# BoostConverter_using_ATmega328P.net
KiCad netlist of a schematic drawn in EAGLE
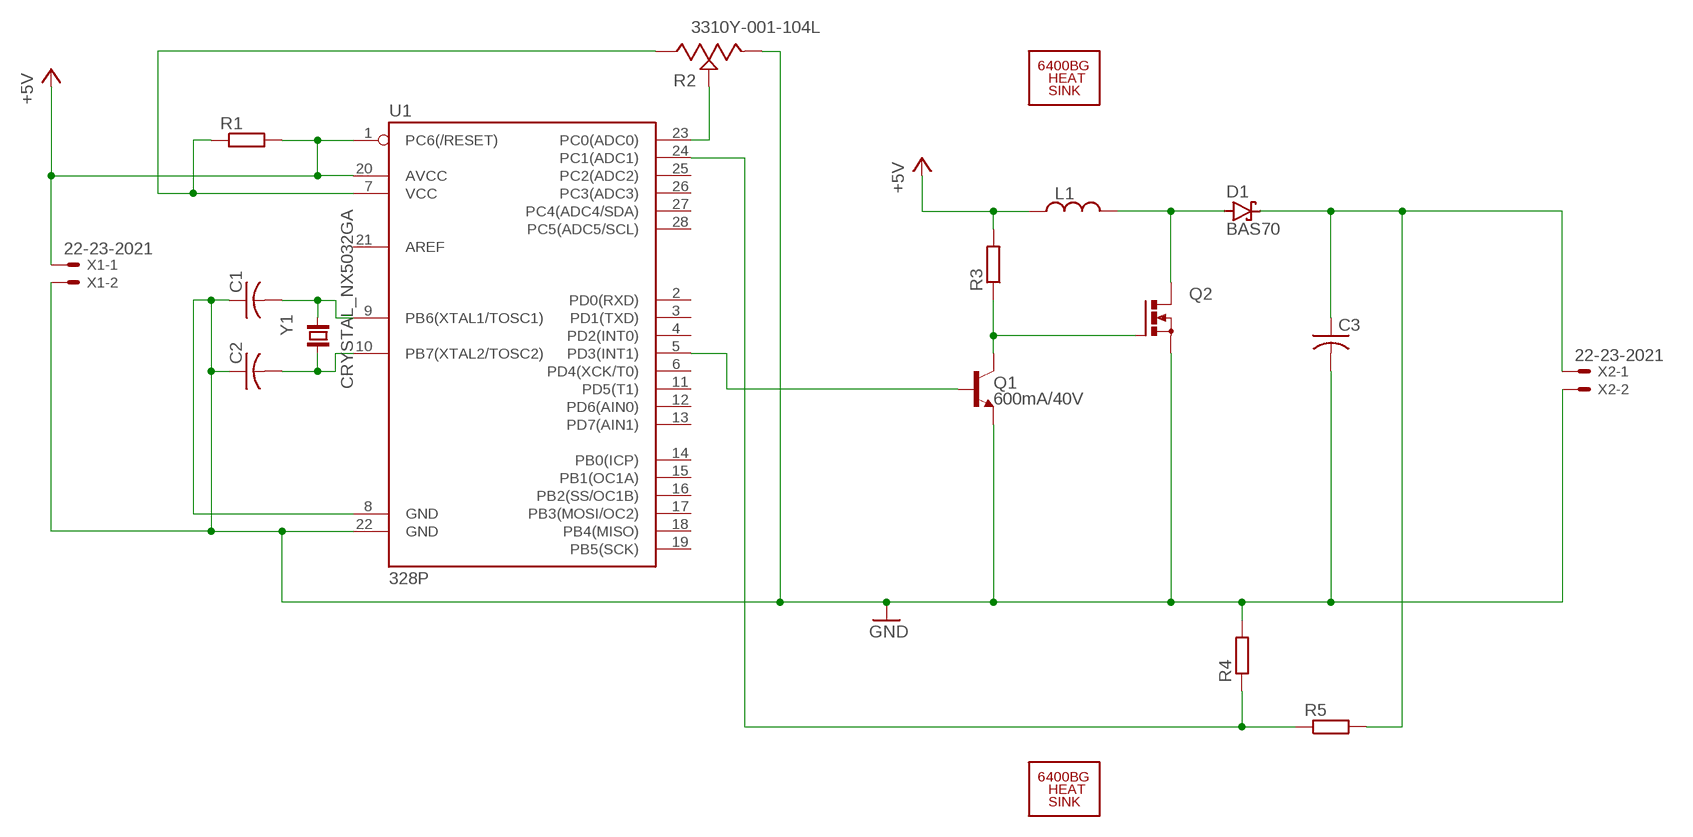
[diagram p0: schematic, sheet 1]

(export (version "E")
  (design (tool "Eeschema 10.0.6"))
  (components
    (comp (ref "C1")
      (value "C-USC0805")
      (footprint "eagle-import:C0805")
      (libsource (lib "eagle-import") (part "C-USC0805"))
    )
    (comp (ref "C2")
      (value "C-USC0805")
      (footprint "eagle-import:C0805")
      (libsource (lib "eagle-import") (part "C-USC0805"))
    )
    (comp (ref "C3")
      (value "C-USC0805")
      (footprint "eagle-import:C0805")
      (libsource (lib "eagle-import") (part "C-USC0805"))
    )
    (comp (ref "D1")
      (value "BAS70")
      (footprint "eagle-import:SOT23")
      (libsource (lib "eagle-import") (part "BAS70"))
    )
    (comp (ref "H1")
      (value "6400BG_HEATSINK")
      (footprint "eagle-import:6400BG_HEATSINK")
      (libsource (lib "eagle-import") (part "6400BG_HEATSINK"))
    )
    (comp (ref "H2")
      (value "6400BG_HEATSINK")
      (footprint "eagle-import:6400BG_HEATSINK")
      (libsource (lib "eagle-import") (part "6400BG_HEATSINK"))
    )
    (comp (ref "L1")
      (value "L_CHIP(4509-METRIC)")
      (footprint "eagle-import:INDC4509X190")
      (libsource (lib "eagle-import") (part "LCHIP(4509-METRIC)_"))
    )
    (comp (ref "Q1")
      (value "600mA/40V")
      (footprint "eagle-import:SOT23-3")
      (libsource (lib "eagle-import") (part "TRANS_NPN-MMBT2222AL"))
    )
    (comp (ref "Q2")
      (value "N-MOSFET-SO8S")
      (footprint "eagle-import:SO-08")
      (libsource (lib "eagle-import") (part "N-MOSFET-SO8S"))
    )
    (comp (ref "R1")
      (value "R-EU_R0805")
      (footprint "eagle-import:R0805")
      (libsource (lib "eagle-import") (part "R-EU_R0805"))
    )
    (comp (ref "R2")
      (value "3310Y-001-104L")
      (footprint "eagle-import:3310Y-001-104L-ND")
      (fields
        (field (name "DIGIKEY_PARTNO") "3310Y-001-104L-ND")
        (field (name "MANUFACTURER") "Bourns Inc.")
        (field (name "CREATED_BY") " PCBLayout.com")
      )
      (libsource (lib "eagle-import") (part "3310Y-001-104L"))
    )
    (comp (ref "R3")
      (value "R-EU_M1406")
      (footprint "eagle-import:M1406")
      (libsource (lib "eagle-import") (part "R-EU_M1406"))
    )
    (comp (ref "R4")
      (value "R-EU_M0805")
      (footprint "eagle-import:M0805")
      (libsource (lib "eagle-import") (part "R-EU_M0805"))
    )
    (comp (ref "R5")
      (value "R-EU_M0805")
      (footprint "eagle-import:M0805")
      (libsource (lib "eagle-import") (part "R-EU_M0805"))
    )
    (comp (ref "U1")
      (value "328P")
      (footprint "eagle-import:DIP28")
      (libsource (lib "eagle-import") (part "ATMEGA328P_PDIP"))
    )
    (comp (ref "X1")
      (value "22-23-2021")
      (footprint "eagle-import:22-23-2021")
      (fields (field (name "MF") "MOLEX"))
      (libsource (lib "eagle-import") (part "22-23-2021"))
    )
    (comp (ref "X2")
      (value "22-23-2021")
      (footprint "eagle-import:22-23-2021")
      (fields (field (name "MF") "MOLEX"))
      (libsource (lib "eagle-import") (part "22-23-2021"))
    )
    (comp (ref "Y1")
      (value "CRYSTAL_NX5032GA")
      (footprint "eagle-import:CRYSTAL_2-SMD-5X3")
      (libsource (lib "eagle-import") (part "CRYSTAL_NX5032GA"))
    )
  )
  (nets
    (net (code "1") (name "+5V") (class "Default")
      (node (ref "L1") (pin "1") (pinfunction "1_1") (pintype "passive"))
      (node (ref "R1") (pin "2") (pinfunction "2_2") (pintype "passive"))
      (node (ref "R3") (pin "2") (pinfunction "2_2") (pintype "passive"))
      (node (ref "U1") (pin "1") (pinfunction "PC6(/RESET)_1") (pintype "bidirectional"))
      (node (ref "U1") (pin "20") (pinfunction "AVCC_20") (pintype "bidirectional"))
      (node (ref "X1") (pin "1") (pinfunction "S_1") (pintype "passive"))
    )
    (net (code "2") (name "GND") (class "Default")
      (node (ref "C1") (pin "1") (pinfunction "1_1") (pintype "passive"))
      (node (ref "C2") (pin "1") (pinfunction "1_1") (pintype "passive"))
      (node (ref "C3") (pin "2") (pinfunction "2_2") (pintype "passive"))
      (node (ref "Q1") (pin "2") (pinfunction "E_2") (pintype "passive"))
      (node (ref "Q2") (pin "1") (pinfunction "S_1") (pintype "passive"))
      (node (ref "Q2") (pin "2") (pinfunction "S_2") (pintype "passive"))
      (node (ref "Q2") (pin "3") (pinfunction "S_3") (pintype "passive"))
      (node (ref "R2") (pin "1") (pinfunction "1_1") (pintype "passive"))
      (node (ref "R4") (pin "2") (pinfunction "2_2") (pintype "passive"))
      (node (ref "U1") (pin "22") (pinfunction "GND_22") (pintype "bidirectional"))
      (node (ref "U1") (pin "8") (pinfunction "GND_8") (pintype "bidirectional"))
      (node (ref "X1") (pin "2") (pinfunction "S_2") (pintype "passive"))
      (node (ref "X2") (pin "2") (pinfunction "S_2") (pintype "passive"))
    )
    (net (code "3") (name "Net-(D1-A)") (class "Default")
      (node (ref "D1") (pin "1") (pinfunction "A_1") (pintype "passive"))
      (node (ref "L1") (pin "2") (pinfunction "2_2") (pintype "passive"))
      (node (ref "Q2") (pin "5") (pinfunction "D_5") (pintype "passive"))
      (node (ref "Q2") (pin "6") (pinfunction "D_6") (pintype "passive"))
      (node (ref "Q2") (pin "7") (pinfunction "D_7") (pintype "passive"))
      (node (ref "Q2") (pin "8") (pinfunction "D_8") (pintype "passive"))
    )
    (net (code "4") (name "Net-(D1-C)") (class "Default")
      (node (ref "C3") (pin "1") (pinfunction "1_1") (pintype "passive"))
      (node (ref "D1") (pin "3") (pinfunction "C_3") (pintype "passive"))
      (node (ref "R5") (pin "2") (pinfunction "2_2") (pintype "passive"))
      (node (ref "X2") (pin "1") (pinfunction "S_1") (pintype "passive"))
    )
    (net (code "5") (name "Net-(Q1-B)") (class "Default")
      (node (ref "Q1") (pin "1") (pinfunction "B_1") (pintype "passive"))
      (node (ref "U1") (pin "5") (pinfunction "PD3(INT1)_5") (pintype "bidirectional"))
    )
    (net (code "6") (name "Net-(Q1-C)") (class "Default")
      (node (ref "Q1") (pin "3") (pinfunction "C_3") (pintype "passive"))
      (node (ref "Q2") (pin "4") (pinfunction "G_4") (pintype "passive"))
      (node (ref "R3") (pin "1") (pinfunction "1_1") (pintype "passive"))
    )
    (net (code "7") (name "Net-(U1-PB6(XTAL1{slash}TOSC1))") (class "Default")
      (node (ref "C1") (pin "2") (pinfunction "2_2") (pintype "passive"))
      (node (ref "U1") (pin "9") (pinfunction "PB6(XTAL1/TOSC1)_9") (pintype "bidirectional"))
      (node (ref "Y1") (pin "2") (pinfunction "2_2") (pintype "passive"))
    )
    (net (code "8") (name "Net-(U1-PB7(XTAL2{slash}TOSC2))") (class "Default")
      (node (ref "C2") (pin "2") (pinfunction "2_2") (pintype "passive"))
      (node (ref "U1") (pin "10") (pinfunction "PB7(XTAL2/TOSC2)_10") (pintype "bidirectional"))
      (node (ref "Y1") (pin "1") (pinfunction "1_1") (pintype "passive"))
    )
    (net (code "9") (name "Net-(U1-PC0(ADC0))") (class "Default")
      (node (ref "R2") (pin "2") (pinfunction "2_2") (pintype "passive"))
      (node (ref "U1") (pin "23") (pinfunction "PC0(ADC0)_23") (pintype "bidirectional"))
    )
    (net (code "10") (name "Net-(U1-PC1(ADC1))") (class "Default")
      (node (ref "R4") (pin "1") (pinfunction "1_1") (pintype "passive"))
      (node (ref "R5") (pin "1") (pinfunction "1_1") (pintype "passive"))
      (node (ref "U1") (pin "24") (pinfunction "PC1(ADC1)_24") (pintype "bidirectional"))
    )
    (net (code "11") (name "Net-(U1-VCC)") (class "Default")
      (node (ref "R1") (pin "1") (pinfunction "1_1") (pintype "passive"))
      (node (ref "R2") (pin "3") (pinfunction "3_3") (pintype "passive"))
      (node (ref "U1") (pin "7") (pinfunction "VCC_7") (pintype "bidirectional"))
    )
    (net (code "12") (name "unconnected-(U1-AREF-Pad21)") (class "Default")
      (node (ref "U1") (pin "21") (pinfunction "AREF_21") (pintype "bidirectional"))
    )
    (net (code "13") (name "unconnected-(U1-PB0(ICP)-Pad14)") (class "Default")
      (node (ref "U1") (pin "14") (pinfunction "PB0(ICP)_14") (pintype "bidirectional"))
    )
    (net (code "14") (name "unconnected-(U1-PB1(OC1A)-Pad15)") (class "Default")
      (node (ref "U1") (pin "15") (pinfunction "PB1(OC1A)_15") (pintype "bidirectional"))
    )
    (net (code "15") (name "unconnected-(U1-PB2(SS{slash}OC1B)-Pad16)") (class "Default")
      (node (ref "U1") (pin "16") (pinfunction "PB2(SS/OC1B)_16") (pintype "bidirectional"))
    )
    (net (code "16") (name "unconnected-(U1-PB3(MOSI{slash}OC2)-Pad17)") (class "Default")
      (node (ref "U1") (pin "17") (pinfunction "PB3(MOSI/OC2)_17") (pintype "bidirectional"))
    )
    (net (code "17") (name "unconnected-(U1-PB4(MISO)-Pad18)") (class "Default")
      (node (ref "U1") (pin "18") (pinfunction "PB4(MISO)_18") (pintype "bidirectional"))
    )
    (net (code "18") (name "unconnected-(U1-PB5(SCK)-Pad19)") (class "Default")
      (node (ref "U1") (pin "19") (pinfunction "PB5(SCK)_19") (pintype "bidirectional"))
    )
    (net (code "19") (name "unconnected-(U1-PC2(ADC2)-Pad25)") (class "Default")
      (node (ref "U1") (pin "25") (pinfunction "PC2(ADC2)_25") (pintype "bidirectional"))
    )
    (net (code "20") (name "unconnected-(U1-PC3(ADC3)-Pad26)") (class "Default")
      (node (ref "U1") (pin "26") (pinfunction "PC3(ADC3)_26") (pintype "bidirectional"))
    )
    (net (code "21") (name "unconnected-(U1-PC4(ADC4{slash}SDA)-Pad27)") (class "Default")
      (node (ref "U1") (pin "27") (pinfunction "PC4(ADC4/SDA)_27") (pintype "bidirectional"))
    )
    (net (code "22") (name "unconnected-(U1-PC5(ADC5{slash}SCL)-Pad28)") (class "Default")
      (node (ref "U1") (pin "28") (pinfunction "PC5(ADC5/SCL)_28") (pintype "bidirectional"))
    )
    (net (code "23") (name "unconnected-(U1-PD0(RXD)-Pad2)") (class "Default")
      (node (ref "U1") (pin "2") (pinfunction "PD0(RXD)_2") (pintype "bidirectional"))
    )
    (net (code "24") (name "unconnected-(U1-PD1(TXD)-Pad3)") (class "Default")
      (node (ref "U1") (pin "3") (pinfunction "PD1(TXD)_3") (pintype "bidirectional"))
    )
    (net (code "25") (name "unconnected-(U1-PD2(INT0)-Pad4)") (class "Default")
      (node (ref "U1") (pin "4") (pinfunction "PD2(INT0)_4") (pintype "bidirectional"))
    )
    (net (code "26") (name "unconnected-(U1-PD4(XCK{slash}T0)-Pad6)") (class "Default")
      (node (ref "U1") (pin "6") (pinfunction "PD4(XCK/T0)_6") (pintype "bidirectional"))
    )
    (net (code "27") (name "unconnected-(U1-PD5(T1)-Pad11)") (class "Default")
      (node (ref "U1") (pin "11") (pinfunction "PD5(T1)_11") (pintype "bidirectional"))
    )
    (net (code "28") (name "unconnected-(U1-PD6(AIN0)-Pad12)") (class "Default")
      (node (ref "U1") (pin "12") (pinfunction "PD6(AIN0)_12") (pintype "bidirectional"))
    )
    (net (code "29") (name "unconnected-(U1-PD7(AIN1)-Pad13)") (class "Default")
      (node (ref "U1") (pin "13") (pinfunction "PD7(AIN1)_13") (pintype "bidirectional"))
    )
  )
)
